# ProjectTest1.net
KiCad netlist of a schematic drawn in Altium Designer
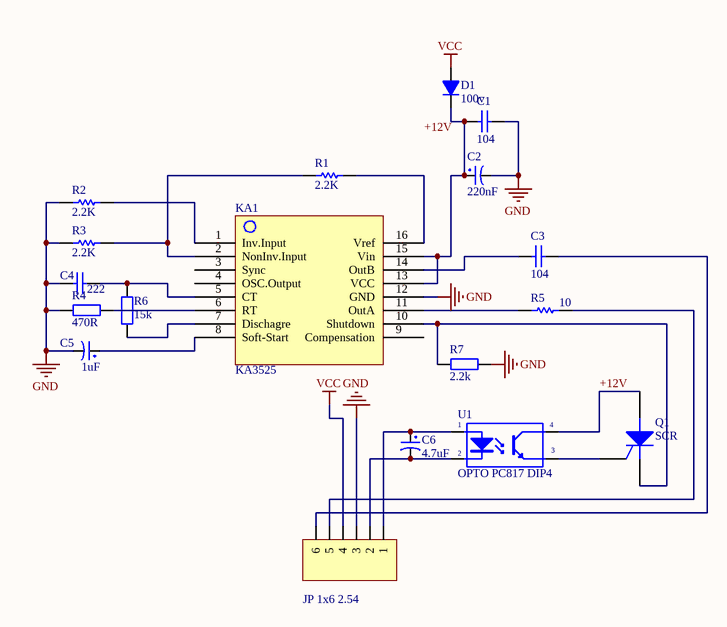
[diagram p0: ProjectTest1.SchDoc]

(export (version "E")
  (design (tool "Eeschema 10.0.6"))
  (components
    (comp (ref "C1")
      (value "104")
      (footprint "tu gom")
      (description "C?m")
      (libsource (lib "Altium_Lib_by_KhueNguyenCreator") (part "Tu gom 104 50V"))
    )
    (comp (ref "C2")
      (value "220nF")
      (footprint "tu hoa 8mm")
      (description "C?m")
      (libsource (lib "Altium_Lib_by_KhueNguyenCreator") (part "Tu Hoa 220uF 35V 8x12"))
    )
    (comp (ref "C3")
      (value "104")
      (footprint "tu gom")
      (description "C?m")
      (libsource (lib "Altium_Lib_by_KhueNguyenCreator") (part "Tu gom 104 50V"))
    )
    (comp (ref "C4")
      (value "222")
      (footprint "tu gom")
      (description "C?m")
      (libsource (lib "Altium_Lib_by_KhueNguyenCreator") (part "Tu gom 222 50V"))
    )
    (comp (ref "C5")
      (value "1uF")
      (footprint "tu hoa 5mm")
      (description "C?m")
      (libsource (lib "Altium_Lib_by_KhueNguyenCreator") (part "Tu Hoa 1uF 50V 5x11"))
    )
    (comp (ref "C6")
      (value "4.7uF")
      (footprint "tu hoa 5mm")
      (description "C?m")
      (libsource (lib "Altium_Lib_by_KhueNguyenCreator") (part "Tu Hoa 4.7uF 50V 5x11"))
    )
    (comp (ref "D1")
      (value "100v")
      (footprint "DIODE 1A")
      (description "C?m")
      (libsource (lib "Altium_Lib_by_KhueNguyenCreator") (part "Diode 1N4007"))
    )
    (comp (ref "JP1")
      (value "JP 1x6 2.54")
      (footprint "JP 1x6 DC")
      (description "C?m")
      (libsource (lib "Altium_Lib_by_KhueNguyenCreator") (part "JP 1x6 2.54 Duc Cong"))
    )
    (comp (ref "KA1") (value "KA3525") (footprint "KA3525-DIP16") (libsource (lib "KA3525") (part "KA3525")))
    (comp (ref "Q1")
      (value "SCR")
      (footprint "QTO-92")
      (description "Silicon Controlled Rectifier")
      (fields (field (name "PUBLISHER") "Altium Limited"))
      (libsource (lib "Miscellaneous Devices") (part "SCR"))
    )
    (comp (ref "R1")
      (value "2.2K")
      (footprint "R1/4W")
      (description "Resistor")
      (fields
        (field (name "MANUFACTURER") "Generic Components")
        (field (name "Comment") "Res1")
        (field (name "PUBLISHER") "Altium Hobart Technology Centre")
      )
      (libsource (lib "Thuvien3D") (part "Res1_1"))
    )
    (comp (ref "R2")
      (value "2.2K")
      (footprint "R1/4W")
      (description "Resistor")
      (fields
        (field (name "MANUFACTURER") "Generic Components")
        (field (name "Comment") "Res1")
        (field (name "PUBLISHER") "Altium Hobart Technology Centre")
      )
      (libsource (lib "Thuvien3D") (part "Res1_1"))
    )
    (comp (ref "R3")
      (value "2.2K")
      (footprint "R1/4W")
      (description "Resistor")
      (fields
        (field (name "MANUFACTURER") "Generic Components")
        (field (name "Comment") "Res1")
        (field (name "PUBLISHER") "Altium Hobart Technology Centre")
      )
      (libsource (lib "Thuvien3D") (part "Res1_1"))
    )
    (comp (ref "R4")
      (value "470R")
      (footprint "tro vach 1/4w")
      (description "C?m")
      (libsource (lib "Altium_Lib_by_KhueNguyenCreator") (part "Tro Vach 1/4W 1% 330R"))
    )
    (comp (ref "R5")
      (value "10")
      (footprint "R1/4W")
      (description "Resistor")
      (fields
        (field (name "MANUFACTURER") "Generic Components")
        (field (name "Comment") "Res1")
        (field (name "PUBLISHER") "Altium Hobart Technology Centre")
      )
      (libsource (lib "Thuvien3D") (part "Res1_1"))
    )
    (comp (ref "R6")
      (value "15k")
      (footprint "tro vach 1/4w")
      (description "C?m")
      (libsource (lib "Altium_Lib_by_KhueNguyenCreator") (part "Tro Vach 1/4W 5% 2.2k"))
    )
    (comp (ref "R7")
      (value "2.2k")
      (footprint "tro vach 1/4w")
      (description "C?m")
      (libsource (lib "Altium_Lib_by_KhueNguyenCreator") (part "Tro Vach 1/4W 5% 2.2k"))
    )
    (comp (ref "U1")
      (value "OPTO PC817 DIP4")
      (footprint "DIP4")
      (description "Single Opto")
      (libsource (lib "Altium_Lib_by_KhueNguyenCreator") (part "OPTO PC817 DIP4"))
    )
  )
  (nets
    (net (code "1") (name "/+12V") (class "Default")
      (node (ref "Q1") (pin "1") (pinfunction "A_1") (pintype "passive"))
      (node (ref "U1") (pin "4") (pinfunction "C_4") (pintype "passive"))
    )
    (net (code "2") (name "GND") (class "Default")
      (node (ref "C1") (pin "1") (pinfunction "1_1") (pintype "passive"))
      (node (ref "C2") (pin "2") (pinfunction "2_2") (pintype "passive"))
      (node (ref "C4") (pin "2") (pinfunction "2_2") (pintype "passive"))
      (node (ref "C5") (pin "2") (pinfunction "2_2") (pintype "passive"))
      (node (ref "JP1") (pin "3") (pinfunction "3_3") (pintype "passive"))
      (node (ref "KA1") (pin "12") (pinfunction "GND_12") (pintype "passive"))
      (node (ref "R2") (pin "2") (pinfunction "2_2") (pintype "passive"))
      (node (ref "R3") (pin "2") (pinfunction "2_2") (pintype "passive"))
      (node (ref "R4") (pin "1") (pinfunction "1_1") (pintype "passive"))
      (node (ref "R7") (pin "2") (pinfunction "2_2") (pintype "passive"))
    )
    (net (code "3") (name "Net-(C3-Pad1)") (class "Default")
      (node (ref "C3") (pin "1") (pinfunction "1_1") (pintype "passive"))
      (node (ref "JP1") (pin "6") (pinfunction "6_6") (pintype "passive"))
    )
    (net (code "4") (name "Net-(D1-K)") (class "Default")
      (node (ref "C1") (pin "2") (pinfunction "2_2") (pintype "passive"))
      (node (ref "C2") (pin "1") (pinfunction "1_1") (pintype "passive"))
      (node (ref "D1") (pin "2") (pinfunction "K_2") (pintype "passive"))
      (node (ref "KA1") (pin "13") (pinfunction "VCC_13") (pintype "passive"))
      (node (ref "KA1") (pin "15") (pinfunction "Vin_15") (pintype "passive"))
    )
    (net (code "5") (name "Net-(JP1-Pad5)") (class "Default")
      (node (ref "JP1") (pin "5") (pinfunction "5_5") (pintype "passive"))
      (node (ref "R5") (pin "1") (pinfunction "1_1") (pintype "passive"))
    )
    (net (code "6") (name "Net-(KA1-CT)") (class "Default")
      (node (ref "C4") (pin "1") (pinfunction "1_1") (pintype "passive"))
      (node (ref "KA1") (pin "5") (pinfunction "CT_5") (pintype "passive"))
      (node (ref "R6") (pin "2") (pinfunction "2_2") (pintype "passive"))
    )
    (net (code "7") (name "Net-(KA1-Dischagre)") (class "Default")
      (node (ref "KA1") (pin "7") (pinfunction "Dischagre_7") (pintype "passive"))
      (node (ref "R6") (pin "1") (pinfunction "1_1") (pintype "passive"))
    )
    (net (code "8") (name "Net-(KA1-Inv.Input)") (class "Default")
      (node (ref "KA1") (pin "1") (pinfunction "Inv.Input_1") (pintype "passive"))
      (node (ref "R2") (pin "1") (pinfunction "1_1") (pintype "passive"))
    )
    (net (code "9") (name "Net-(KA1-NonInv.Input)") (class "Default")
      (node (ref "KA1") (pin "2") (pinfunction "NonInv.Input_2") (pintype "passive"))
      (node (ref "R1") (pin "2") (pinfunction "2_2") (pintype "passive"))
      (node (ref "R3") (pin "1") (pinfunction "1_1") (pintype "passive"))
    )
    (net (code "10") (name "Net-(KA1-OutA)") (class "Default")
      (node (ref "KA1") (pin "11") (pinfunction "OutA_11") (pintype "passive"))
      (node (ref "R5") (pin "2") (pinfunction "2_2") (pintype "passive"))
    )
    (net (code "11") (name "Net-(KA1-OutB)") (class "Default")
      (node (ref "C3") (pin "2") (pinfunction "2_2") (pintype "passive"))
      (node (ref "KA1") (pin "14") (pinfunction "OutB_14") (pintype "passive"))
    )
    (net (code "12") (name "Net-(KA1-RT)") (class "Default")
      (node (ref "KA1") (pin "6") (pinfunction "RT_6") (pintype "passive"))
      (node (ref "R4") (pin "2") (pinfunction "2_2") (pintype "passive"))
    )
    (net (code "13") (name "Net-(KA1-Shutdown)") (class "Default")
      (node (ref "KA1") (pin "10") (pinfunction "Shutdown_10") (pintype "passive"))
      (node (ref "Q1") (pin "3") (pinfunction "K_3") (pintype "passive"))
      (node (ref "R7") (pin "1") (pinfunction "1_1") (pintype "passive"))
    )
    (net (code "14") (name "Net-(KA1-Soft-Start)") (class "Default")
      (node (ref "C5") (pin "1") (pinfunction "1_1") (pintype "passive"))
      (node (ref "KA1") (pin "8") (pinfunction "Soft-Start_8") (pintype "passive"))
    )
    (net (code "15") (name "Net-(KA1-Vref)") (class "Default")
      (node (ref "KA1") (pin "16") (pinfunction "Vref_16") (pintype "passive"))
      (node (ref "R1") (pin "1") (pinfunction "1_1") (pintype "passive"))
    )
    (net (code "16") (name "Net-(Q1-G)") (class "Default")
      (node (ref "Q1") (pin "2") (pinfunction "G_2") (pintype "passive"))
      (node (ref "U1") (pin "3") (pinfunction "E_3") (pintype "passive"))
    )
    (net (code "17") (name "Net-(U1-A)") (class "Default")
      (node (ref "C6") (pin "1") (pinfunction "1_1") (pintype "passive"))
      (node (ref "JP1") (pin "1") (pinfunction "1_1") (pintype "passive"))
      (node (ref "U1") (pin "1") (pinfunction "A_1") (pintype "passive"))
    )
    (net (code "18") (name "Net-(U1-K)") (class "Default")
      (node (ref "C6") (pin "2") (pinfunction "2_2") (pintype "passive"))
      (node (ref "JP1") (pin "2") (pinfunction "2_2") (pintype "passive"))
      (node (ref "U1") (pin "2") (pinfunction "K_2") (pintype "passive"))
    )
    (net (code "19") (name "VCC") (class "Default")
      (node (ref "D1") (pin "1") (pinfunction "A_1") (pintype "passive"))
      (node (ref "JP1") (pin "4") (pinfunction "4_4") (pintype "passive"))
    )
    (net (code "20") (name "unconnected-(KA1-Compensation-Pad9)") (class "Default")
      (node (ref "KA1") (pin "9") (pinfunction "Compensation_9") (pintype "passive"))
    )
    (net (code "21") (name "unconnected-(KA1-OSC.Output-Pad4)") (class "Default")
      (node (ref "KA1") (pin "4") (pinfunction "OSC.Output_4") (pintype "passive"))
    )
    (net (code "22") (name "unconnected-(KA1-Sync-Pad3)") (class "Default")
      (node (ref "KA1") (pin "3") (pinfunction "Sync_3") (pintype "passive"))
    )
  )
)
